# Power.net
KiCad netlist of a schematic drawn in Altium Designer
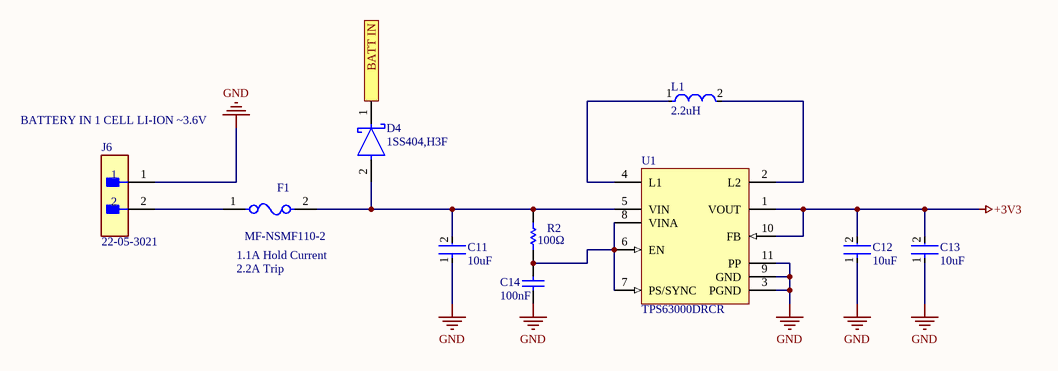
[diagram p0: Power.SchDoc]

(export (version "E")
  (design (tool "Eeschema 10.0.6"))
  (components
    (comp (ref "C11")
      (value "10uF")
      (footprint "FP-C1608-080-IPC_A")
      (description "CAP CER 10UF 25V X5R 0603")
      (fields (field (name "TOLERANCE") "20%"))
      (libsource (lib "Altium Content Vault") (part "11868f565c42a9108669ba33697ecf6"))
    )
    (comp (ref "C12")
      (value "10uF")
      (footprint "FP-C1608-080-IPC_A")
      (description "CAP CER 10UF 25V X5R 0603")
      (fields (field (name "TOLERANCE") "20%"))
      (libsource (lib "Altium Content Vault") (part "11868f565c42a9108669ba33697ecf6"))
    )
    (comp (ref "C13")
      (value "10uF")
      (footprint "FP-C1608-080-IPC_A")
      (description "CAP CER 10UF 25V X5R 0603")
      (fields (field (name "TOLERANCE") "20%"))
      (libsource (lib "Altium Content Vault") (part "11868f565c42a9108669ba33697ecf6"))
    )
    (comp (ref "C14")
      (value "100nF")
      (footprint "CAPC1608X10N")
      (description "Cap Ceramic 0.1uF 50V X7R 20% SMD 0603 125C T/R")
      (fields (field (name "TOLERANCE") "20%") (field (name "Comment") "C0603C104M5RACTU"))
      (libsource (lib "UWA Aerospace") (part "C0603C104M5RACTU"))
    )
    (comp (ref "D4")
      (value "1SS404,H3F")
      (footprint "FP-SOD-323-MFG")
      (description "DIODE SCHOTTKY 20V 300MA USC")
      (libsource (lib "Altium Content Vault") (part "1d6ec82d83fb6aee721767c19dac4b9"))
    )
    (comp (ref "F1")
      (value "MF-NSMF110-2")
      (footprint "FP-MF-NSMF110-2-MFG")
      (description "PTC RESET FUSE 6V 1.1A 1206")
      (fields
        (field (name "OCTOPART") "https://octopart.com/mf-nsmf110-2-bourns-41795")
        (field (name "MANUFACTURER") "Bourns")
      )
      (libsource (lib "Altium Content Vault") (part "5bcf9b9f640e542cf0359d10258e979"))
    )
    (comp (ref "J6")
      (value "22-05-3021")
      (footprint "FP-22-05-3021-MFG")
      (description "CONN HEADER R/A 2POS 2.54MM")
      (libsource (lib "Altium Content Vault") (part "3bc925449376181038e59eaffc5286c"))
    )
    (comp (ref "L1")
      (value "2.2uH")
      (footprint "FP-IHLP-2525BD-FP_2_413x3-MFG")
      (description "Commercial Inductors, High Saturation Series 2.2uH 6.5A 34mΩ 20%")
      (fields (field (name "TOLERANCE") "20%"))
      (libsource (lib "Altium Content Vault") (part "725321dda6339637d4d059423bc1c3c"))
    )
    (comp (ref "R2")
      (value "100Ω")
      (footprint "RESC1609X50X30ML8T20")
      (description "Chip Resistor, 100 Ohm, +/- 1%, 100 mW,-55 to 155 degC, 0603 (1608 Metric), RoHS, Tape and Ree")
      (fields (field (name "MANUFACTURER") "Vishay Semiconductor"))
      (libsource (lib "Altium Content Vault") (part "RES-2"))
    )
    (comp (ref "U1")
      (value "TPS63000DRCR")
      (footprint "DRC0010J_V")
      (description "Switching Regulator, Current-mode, 0.8A, 1500kHz Switching Freq-Max, PDSO10")
      (libsource (lib "Design 1 Group 15") (part "TI-TPS63000DRC10-3000X1650TP"))
    )
  )
  (nets
    (net (code "1") (name "+3V3") (class "Default")
      (node (ref "C12") (pin "2") (pinfunction "2_2") (pintype "passive"))
      (node (ref "C13") (pin "2") (pinfunction "2_2") (pintype "passive"))
      (node (ref "U1") (pin "1") (pinfunction "VOUT_1") (pintype "power_in"))
      (node (ref "U1") (pin "10") (pinfunction "FB_10") (pintype "input"))
    )
    (net (code "2") (name "/BATT IN") (class "Default")
      (node (ref "D4") (pin "1") (pinfunction "C_1") (pintype "passive"))
    )
    (net (code "3") (name "GND") (class "Default")
      (node (ref "C11") (pin "1") (pinfunction "1_1") (pintype "passive"))
      (node (ref "C12") (pin "1") (pinfunction "1_1") (pintype "passive"))
      (node (ref "C13") (pin "1") (pinfunction "1_1") (pintype "passive"))
      (node (ref "C14") (pin "1") (pinfunction "1_1") (pintype "passive"))
      (node (ref "J6") (pin "1") (pinfunction "1_1") (pintype "passive"))
      (node (ref "U1") (pin "11") (pinfunction "PP_11") (pintype "power_in"))
      (node (ref "U1") (pin "3") (pinfunction "PGND_3") (pintype "power_in"))
      (node (ref "U1") (pin "9") (pinfunction "GND_9") (pintype "power_in"))
    )
    (net (code "4") (name "Net-(D4-A)") (class "Default")
      (node (ref "C11") (pin "2") (pinfunction "2_2") (pintype "passive"))
      (node (ref "D4") (pin "2") (pinfunction "A_2") (pintype "passive"))
      (node (ref "F1") (pin "2") (pinfunction "2_2") (pintype "passive"))
      (node (ref "R2") (pin "2") (pinfunction "2_2") (pintype "passive"))
      (node (ref "U1") (pin "5") (pinfunction "VIN_5") (pintype "power_in"))
    )
    (net (code "5") (name "Net-(F1-Pad1)") (class "Default")
      (node (ref "F1") (pin "1") (pinfunction "1_1") (pintype "passive"))
      (node (ref "J6") (pin "2") (pinfunction "2_2") (pintype "passive"))
    )
    (net (code "6") (name "Net-(U1-EN)") (class "Default")
      (node (ref "C14") (pin "2") (pinfunction "2_2") (pintype "passive"))
      (node (ref "R2") (pin "1") (pinfunction "1_1") (pintype "passive"))
      (node (ref "U1") (pin "6") (pinfunction "EN_6") (pintype "input"))
      (node (ref "U1") (pin "7") (pinfunction "PS/SYNC_7") (pintype "input"))
      (node (ref "U1") (pin "8") (pinfunction "VINA_8") (pintype "power_in"))
    )
    (net (code "7") (name "Net-(U1-L1)") (class "Default")
      (node (ref "L1") (pin "1") (pinfunction "1_1") (pintype "passive"))
      (node (ref "U1") (pin "4") (pinfunction "L1_4") (pintype "passive"))
    )
    (net (code "8") (name "Net-(U1-L2)") (class "Default")
      (node (ref "L1") (pin "2") (pinfunction "2_2") (pintype "passive"))
      (node (ref "U1") (pin "2") (pinfunction "L2_2") (pintype "passive"))
    )
  )
)
